# Power.net
KiCad netlist of a schematic drawn in Altium Designer
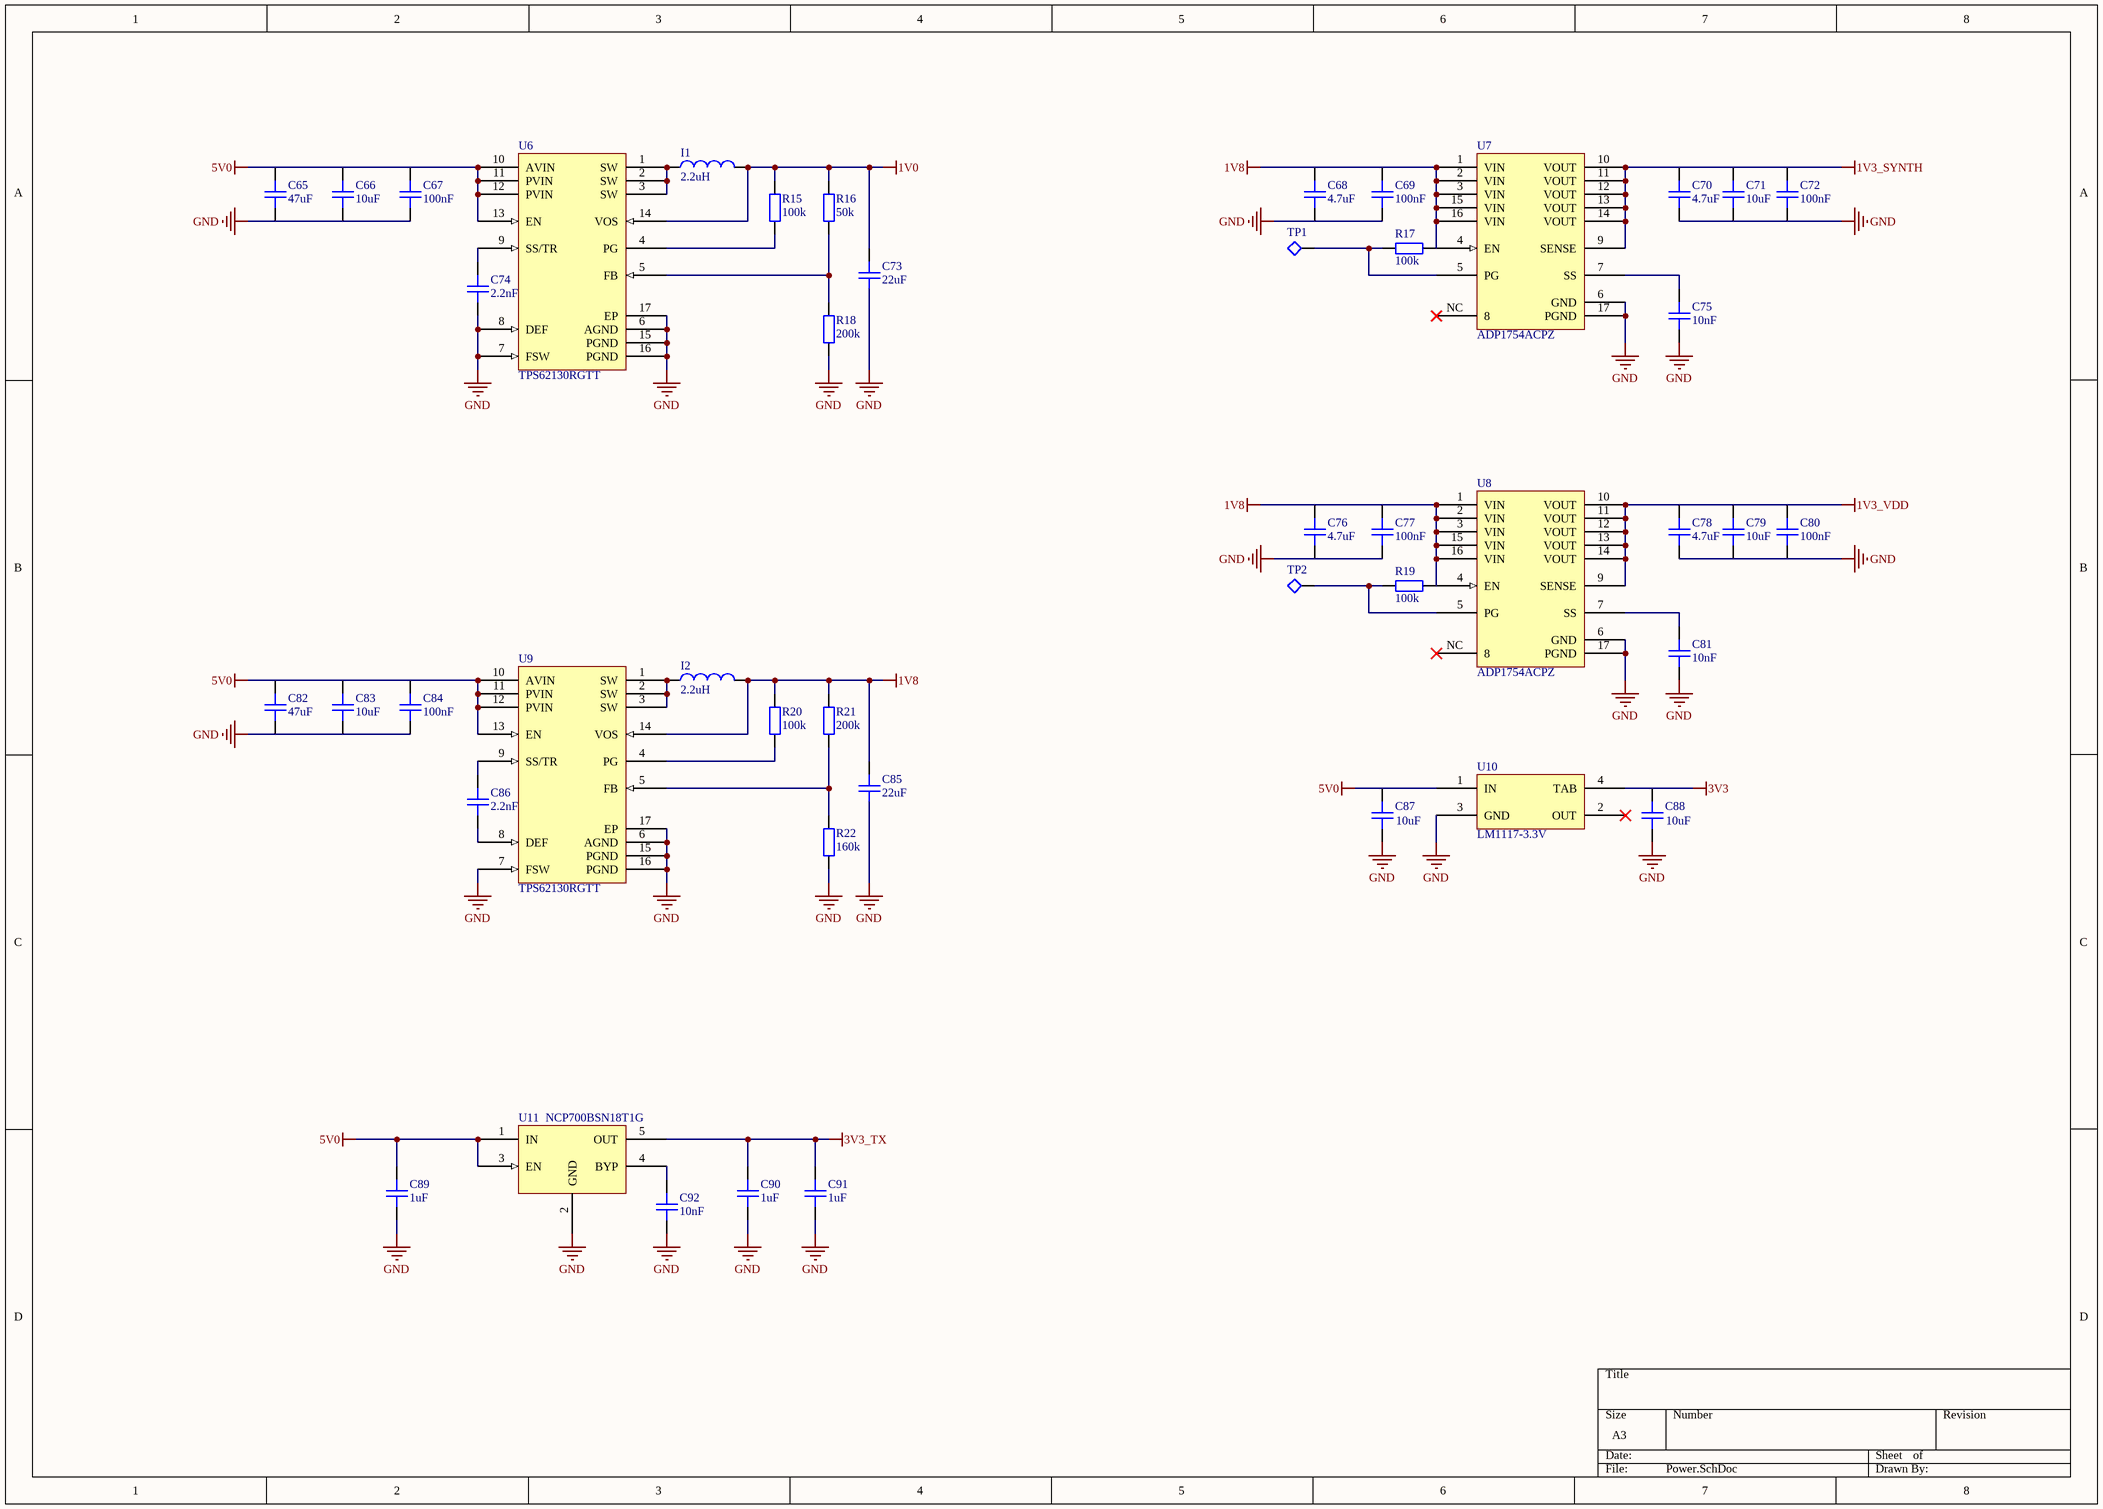
[diagram p0: Power.SchDoc]

(export (version "E")
  (design (tool "Eeschema 10.0.6"))
  (components
    (comp (ref "C65") (value "47uF") (footprint "CAP0402") (libsource (lib "WaveRadio") (part "Cap_0402")))
    (comp (ref "C66") (value "10uF") (footprint "CAP0402") (libsource (lib "WaveRadio") (part "Cap_0402")))
    (comp (ref "C67") (value "100nF") (footprint "CAP0402") (libsource (lib "WaveRadio") (part "Cap_0402")))
    (comp (ref "C68") (value "4.7uF") (footprint "CAP0402") (libsource (lib "WaveRadio") (part "Cap_0402")))
    (comp (ref "C69") (value "100nF") (footprint "CAP0402") (libsource (lib "WaveRadio") (part "Cap_0402")))
    (comp (ref "C70") (value "4.7uF") (footprint "CAP0402") (libsource (lib "WaveRadio") (part "Cap_0402")))
    (comp (ref "C71") (value "10uF") (footprint "CAP0402") (libsource (lib "WaveRadio") (part "Cap_0402")))
    (comp (ref "C72") (value "100nF") (footprint "CAP0402") (libsource (lib "WaveRadio") (part "Cap_0402")))
    (comp (ref "C73") (value "22uF") (footprint "CAP0402") (libsource (lib "WaveRadio") (part "Cap_0402")))
    (comp (ref "C74") (value "2.2nF") (footprint "CAP0402") (libsource (lib "WaveRadio") (part "Cap_0402")))
    (comp (ref "C75") (value "10nF") (footprint "CAP0402") (libsource (lib "WaveRadio") (part "Cap_0402")))
    (comp (ref "C76") (value "4.7uF") (footprint "CAP0402") (libsource (lib "WaveRadio") (part "Cap_0402")))
    (comp (ref "C77") (value "100nF") (footprint "CAP0402") (libsource (lib "WaveRadio") (part "Cap_0402")))
    (comp (ref "C78") (value "4.7uF") (footprint "CAP0402") (libsource (lib "WaveRadio") (part "Cap_0402")))
    (comp (ref "C79") (value "10uF") (footprint "CAP0402") (libsource (lib "WaveRadio") (part "Cap_0402")))
    (comp (ref "C80") (value "100nF") (footprint "CAP0402") (libsource (lib "WaveRadio") (part "Cap_0402")))
    (comp (ref "C81") (value "10nF") (footprint "CAP0402") (libsource (lib "WaveRadio") (part "Cap_0402")))
    (comp (ref "C82") (value "47uF") (footprint "CAP0402") (libsource (lib "WaveRadio") (part "Cap_0402")))
    (comp (ref "C83") (value "10uF") (footprint "CAP0402") (libsource (lib "WaveRadio") (part "Cap_0402")))
    (comp (ref "C84") (value "100nF") (footprint "CAP0402") (libsource (lib "WaveRadio") (part "Cap_0402")))
    (comp (ref "C85") (value "22uF") (footprint "CAP0402") (libsource (lib "WaveRadio") (part "Cap_0402")))
    (comp (ref "C86") (value "2.2nF") (footprint "CAP0402") (libsource (lib "WaveRadio") (part "Cap_0402")))
    (comp (ref "C87") (value "10uF") (footprint "CAP0402") (libsource (lib "WaveRadio") (part "Cap_0402")))
    (comp (ref "C88") (value "10uF") (footprint "CAP0402") (libsource (lib "WaveRadio") (part "Cap_0402")))
    (comp (ref "C89") (value "1uF") (footprint "CAP0402") (libsource (lib "WaveRadio") (part "Cap_0402")))
    (comp (ref "C90") (value "1uF") (footprint "CAP0402") (libsource (lib "WaveRadio") (part "Cap_0402")))
    (comp (ref "C91") (value "1uF") (footprint "CAP0402") (libsource (lib "WaveRadio") (part "Cap_0402")))
    (comp (ref "C92") (value "10nF") (footprint "CAP0402") (libsource (lib "WaveRadio") (part "Cap_0402")))
    (comp (ref "I1")
      (value "2.2uH")
      (fields (field (name "PART") "MLP2012H2R2MT0S1"))
      (libsource (lib "WaveRadio") (part "Ind_0805"))
    )
    (comp (ref "I2")
      (value "2.2uH")
      (fields (field (name "PART") "MLP2012H2R2MT0S1"))
      (libsource (lib "WaveRadio") (part "Ind_0805"))
    )
    (comp (ref "R15") (value "100k") (footprint "RES0402") (libsource (lib "WaveRadio") (part "Res_0402")))
    (comp (ref "R16") (value "50k") (footprint "RES0402") (libsource (lib "WaveRadio") (part "Res_0402")))
    (comp (ref "R17") (value "100k") (footprint "RES0402") (libsource (lib "WaveRadio") (part "Res_0402")))
    (comp (ref "R18") (value "200k") (footprint "RES0402") (libsource (lib "WaveRadio") (part "Res_0402")))
    (comp (ref "R19") (value "100k") (footprint "RES0402") (libsource (lib "WaveRadio") (part "Res_0402")))
    (comp (ref "R20") (value "100k") (footprint "RES0402") (libsource (lib "WaveRadio") (part "Res_0402")))
    (comp (ref "R21") (value "200k") (footprint "RES0402") (libsource (lib "WaveRadio") (part "Res_0402")))
    (comp (ref "R22") (value "160k") (footprint "RES0402") (libsource (lib "WaveRadio") (part "Res_0402")))
    (comp (ref "TP1") (value "TP") (libsource (lib "WaveRadio") (part "TP")))
    (comp (ref "TP2") (value "TP") (libsource (lib "WaveRadio") (part "TP")))
    (comp (ref "U6")
      (value "TPS62130RGTT")
      (footprint "QFN50P300X300X80_HS-17N")
      (libsource (lib "WaveRadio") (part "TPS62130RGTT"))
    )
    (comp (ref "U7")
      (value "ADP1754ACPZ")
      (footprint "QFN65P400X400X80_HS-17N")
      (libsource (lib "WaveRadio") (part "ADP1754ACPZ"))
    )
    (comp (ref "U8")
      (value "ADP1754ACPZ")
      (footprint "QFN65P400X400X80_HS-17N")
      (libsource (lib "WaveRadio") (part "ADP1754ACPZ"))
    )
    (comp (ref "U9")
      (value "TPS62130RGTT")
      (footprint "QFN50P300X300X80_HS-17N")
      (libsource (lib "WaveRadio") (part "TPS62130RGTT"))
    )
    (comp (ref "U10") (value "LM1117-3.3V") (libsource (lib "WaveRadio") (part "LM1117-3.3V")))
    (comp (ref "U11") (value "NCP700BSN18T1G") (libsource (lib "WaveRadio") (part "NCP700BSN18T1G")))
  )
  (nets
    (net (code "1") (name "1V0") (class "Default")
      (node (ref "I1") (pin "2") (pinfunction "2_2") (pintype "passive"))
      (node (ref "U6") (pin "14") (pinfunction "VOS_14") (pintype "input"))
    )
    (net (code "2") (name "1V3_SYNTH") (class "Default")
      (node (ref "U7") (pin "10") (pinfunction "VOUT_10") (pintype "passive"))
      (node (ref "U7") (pin "11") (pinfunction "VOUT_11") (pintype "passive"))
      (node (ref "U7") (pin "12") (pinfunction "VOUT_12") (pintype "passive"))
      (node (ref "U7") (pin "13") (pinfunction "VOUT_13") (pintype "passive"))
      (node (ref "U7") (pin "14") (pinfunction "VOUT_14") (pintype "passive"))
      (node (ref "U7") (pin "9") (pinfunction "SENSE_9") (pintype "passive"))
    )
    (net (code "3") (name "1V3_VDD") (class "Default")
      (node (ref "U8") (pin "10") (pinfunction "VOUT_10") (pintype "passive"))
      (node (ref "U8") (pin "11") (pinfunction "VOUT_11") (pintype "passive"))
      (node (ref "U8") (pin "12") (pinfunction "VOUT_12") (pintype "passive"))
      (node (ref "U8") (pin "13") (pinfunction "VOUT_13") (pintype "passive"))
      (node (ref "U8") (pin "14") (pinfunction "VOUT_14") (pintype "passive"))
      (node (ref "U8") (pin "9") (pinfunction "SENSE_9") (pintype "passive"))
    )
    (net (code "4") (name "1V8") (class "Default")
      (node (ref "I2") (pin "2") (pinfunction "2_2") (pintype "passive"))
      (node (ref "U7") (pin "1") (pinfunction "VIN_1") (pintype "passive"))
      (node (ref "U7") (pin "15") (pinfunction "VIN_15") (pintype "passive"))
      (node (ref "U7") (pin "16") (pinfunction "VIN_16") (pintype "passive"))
      (node (ref "U7") (pin "2") (pinfunction "VIN_2") (pintype "passive"))
      (node (ref "U7") (pin "3") (pinfunction "VIN_3") (pintype "passive"))
      (node (ref "U7") (pin "4") (pinfunction "EN_4") (pintype "input"))
      (node (ref "U8") (pin "1") (pinfunction "VIN_1") (pintype "passive"))
      (node (ref "U8") (pin "15") (pinfunction "VIN_15") (pintype "passive"))
      (node (ref "U8") (pin "16") (pinfunction "VIN_16") (pintype "passive"))
      (node (ref "U8") (pin "2") (pinfunction "VIN_2") (pintype "passive"))
      (node (ref "U8") (pin "3") (pinfunction "VIN_3") (pintype "passive"))
      (node (ref "U8") (pin "4") (pinfunction "EN_4") (pintype "input"))
      (node (ref "U9") (pin "14") (pinfunction "VOS_14") (pintype "input"))
    )
    (net (code "5") (name "3V3") (class "Default")
      (node (ref "U10") (pin "4") (pinfunction "TAB_4") (pintype "passive"))
    )
    (net (code "6") (name "3V3_TX") (class "Default")
      (node (ref "U11") (pin "5") (pinfunction "OUT_5") (pintype "passive"))
    )
    (net (code "7") (name "5V0") (class "Default")
      (node (ref "U10") (pin "1") (pinfunction "IN_1") (pintype "passive"))
      (node (ref "U11") (pin "1") (pinfunction "IN_1") (pintype "passive"))
      (node (ref "U11") (pin "3") (pinfunction "EN_3") (pintype "input"))
      (node (ref "U6") (pin "10") (pinfunction "AVIN_10") (pintype "passive"))
      (node (ref "U6") (pin "11") (pinfunction "PVIN_11") (pintype "passive"))
      (node (ref "U6") (pin "12") (pinfunction "PVIN_12") (pintype "passive"))
      (node (ref "U6") (pin "13") (pinfunction "EN_13") (pintype "input"))
      (node (ref "U9") (pin "10") (pinfunction "AVIN_10") (pintype "passive"))
      (node (ref "U9") (pin "11") (pinfunction "PVIN_11") (pintype "passive"))
      (node (ref "U9") (pin "12") (pinfunction "PVIN_12") (pintype "passive"))
      (node (ref "U9") (pin "13") (pinfunction "EN_13") (pintype "input"))
    )
    (net (code "8") (name "GND") (class "Default")
      (node (ref "C73") (pin "1") (pinfunction "1_1") (pintype "passive"))
      (node (ref "C85") (pin "1") (pinfunction "1_1") (pintype "passive"))
      (node (ref "U10") (pin "3") (pinfunction "GND_3") (pintype "passive"))
      (node (ref "U11") (pin "2") (pinfunction "GND_2") (pintype "passive"))
      (node (ref "U6") (pin "15") (pinfunction "PGND_15") (pintype "passive"))
      (node (ref "U6") (pin "16") (pinfunction "PGND_16") (pintype "passive"))
      (node (ref "U6") (pin "17") (pinfunction "EP_17") (pintype "passive"))
      (node (ref "U6") (pin "6") (pinfunction "AGND_6") (pintype "passive"))
      (node (ref "U6") (pin "7") (pinfunction "FSW_7") (pintype "input"))
      (node (ref "U6") (pin "8") (pinfunction "DEF_8") (pintype "input"))
      (node (ref "U7") (pin "17") (pinfunction "PGND_17") (pintype "passive"))
      (node (ref "U7") (pin "6") (pinfunction "GND_6") (pintype "passive"))
      (node (ref "U8") (pin "17") (pinfunction "PGND_17") (pintype "passive"))
      (node (ref "U8") (pin "6") (pinfunction "GND_6") (pintype "passive"))
      (node (ref "U9") (pin "15") (pinfunction "PGND_15") (pintype "passive"))
      (node (ref "U9") (pin "16") (pinfunction "PGND_16") (pintype "passive"))
      (node (ref "U9") (pin "17") (pinfunction "EP_17") (pintype "passive"))
      (node (ref "U9") (pin "6") (pinfunction "AGND_6") (pintype "passive"))
      (node (ref "U9") (pin "7") (pinfunction "FSW_7") (pintype "input"))
    )
    (net (code "9") (name "Net-(I1-Pad1)") (class "Default")
      (node (ref "I1") (pin "1") (pinfunction "1_1") (pintype "passive"))
      (node (ref "U6") (pin "1") (pinfunction "SW_1") (pintype "passive"))
      (node (ref "U6") (pin "2") (pinfunction "SW_2") (pintype "passive"))
      (node (ref "U6") (pin "3") (pinfunction "SW_3") (pintype "passive"))
    )
    (net (code "10") (name "Net-(I2-Pad1)") (class "Default")
      (node (ref "I2") (pin "1") (pinfunction "1_1") (pintype "passive"))
      (node (ref "U9") (pin "1") (pinfunction "SW_1") (pintype "passive"))
      (node (ref "U9") (pin "2") (pinfunction "SW_2") (pintype "passive"))
      (node (ref "U9") (pin "3") (pinfunction "SW_3") (pintype "passive"))
    )
    (net (code "11") (name "Net-(TP1-NC)") (class "Default")
      (node (ref "TP1") (pin "1") (pinfunction "NC_1") (pintype "passive"))
      (node (ref "U7") (pin "5") (pinfunction "PG_5") (pintype "passive"))
    )
    (net (code "12") (name "Net-(TP2-NC)") (class "Default")
      (node (ref "TP2") (pin "1") (pinfunction "NC_1") (pintype "passive"))
      (node (ref "U8") (pin "5") (pinfunction "PG_5") (pintype "passive"))
    )
    (net (code "13") (name "unconnected-(C65-Pad1)") (class "Default")
      (node (ref "C65") (pin "1") (pinfunction "1_1") (pintype "passive"))
    )
    (net (code "14") (name "unconnected-(C65-Pad2)") (class "Default")
      (node (ref "C65") (pin "2") (pinfunction "2_2") (pintype "passive"))
    )
    (net (code "15") (name "unconnected-(C66-Pad1)") (class "Default")
      (node (ref "C66") (pin "1") (pinfunction "1_1") (pintype "passive"))
    )
    (net (code "16") (name "unconnected-(C66-Pad2)") (class "Default")
      (node (ref "C66") (pin "2") (pinfunction "2_2") (pintype "passive"))
    )
    (net (code "17") (name "unconnected-(C67-Pad1)") (class "Default")
      (node (ref "C67") (pin "1") (pinfunction "1_1") (pintype "passive"))
    )
    (net (code "18") (name "unconnected-(C67-Pad2)") (class "Default")
      (node (ref "C67") (pin "2") (pinfunction "2_2") (pintype "passive"))
    )
    (net (code "19") (name "unconnected-(C68-Pad1)") (class "Default")
      (node (ref "C68") (pin "1") (pinfunction "1_1") (pintype "passive"))
    )
    (net (code "20") (name "unconnected-(C68-Pad2)") (class "Default")
      (node (ref "C68") (pin "2") (pinfunction "2_2") (pintype "passive"))
    )
    (net (code "21") (name "unconnected-(C69-Pad1)") (class "Default")
      (node (ref "C69") (pin "1") (pinfunction "1_1") (pintype "passive"))
    )
    (net (code "22") (name "unconnected-(C69-Pad2)") (class "Default")
      (node (ref "C69") (pin "2") (pinfunction "2_2") (pintype "passive"))
    )
    (net (code "23") (name "unconnected-(C70-Pad1)") (class "Default")
      (node (ref "C70") (pin "1") (pinfunction "1_1") (pintype "passive"))
    )
    (net (code "24") (name "unconnected-(C70-Pad2)") (class "Default")
      (node (ref "C70") (pin "2") (pinfunction "2_2") (pintype "passive"))
    )
    (net (code "25") (name "unconnected-(C71-Pad1)") (class "Default")
      (node (ref "C71") (pin "1") (pinfunction "1_1") (pintype "passive"))
    )
    (net (code "26") (name "unconnected-(C71-Pad2)") (class "Default")
      (node (ref "C71") (pin "2") (pinfunction "2_2") (pintype "passive"))
    )
    (net (code "27") (name "unconnected-(C72-Pad1)") (class "Default")
      (node (ref "C72") (pin "1") (pinfunction "1_1") (pintype "passive"))
    )
    (net (code "28") (name "unconnected-(C72-Pad2)") (class "Default")
      (node (ref "C72") (pin "2") (pinfunction "2_2") (pintype "passive"))
    )
    (net (code "29") (name "unconnected-(C73-Pad2)") (class "Default")
      (node (ref "C73") (pin "2") (pinfunction "2_2") (pintype "passive"))
    )
    (net (code "30") (name "unconnected-(C74-Pad1)") (class "Default")
      (node (ref "C74") (pin "1") (pinfunction "1_1") (pintype "passive"))
    )
    (net (code "31") (name "unconnected-(C74-Pad2)") (class "Default")
      (node (ref "C74") (pin "2") (pinfunction "2_2") (pintype "passive"))
    )
    (net (code "32") (name "unconnected-(C75-Pad1)") (class "Default")
      (node (ref "C75") (pin "1") (pinfunction "1_1") (pintype "passive"))
    )
    (net (code "33") (name "unconnected-(C75-Pad2)") (class "Default")
      (node (ref "C75") (pin "2") (pinfunction "2_2") (pintype "passive"))
    )
    (net (code "34") (name "unconnected-(C76-Pad1)") (class "Default")
      (node (ref "C76") (pin "1") (pinfunction "1_1") (pintype "passive"))
    )
    (net (code "35") (name "unconnected-(C76-Pad2)") (class "Default")
      (node (ref "C76") (pin "2") (pinfunction "2_2") (pintype "passive"))
    )
    (net (code "36") (name "unconnected-(C77-Pad1)") (class "Default")
      (node (ref "C77") (pin "1") (pinfunction "1_1") (pintype "passive"))
    )
    (net (code "37") (name "unconnected-(C77-Pad2)") (class "Default")
      (node (ref "C77") (pin "2") (pinfunction "2_2") (pintype "passive"))
    )
    (net (code "38") (name "unconnected-(C78-Pad1)") (class "Default")
      (node (ref "C78") (pin "1") (pinfunction "1_1") (pintype "passive"))
    )
    (net (code "39") (name "unconnected-(C78-Pad2)") (class "Default")
      (node (ref "C78") (pin "2") (pinfunction "2_2") (pintype "passive"))
    )
    (net (code "40") (name "unconnected-(C79-Pad1)") (class "Default")
      (node (ref "C79") (pin "1") (pinfunction "1_1") (pintype "passive"))
    )
    (net (code "41") (name "unconnected-(C79-Pad2)") (class "Default")
      (node (ref "C79") (pin "2") (pinfunction "2_2") (pintype "passive"))
    )
    (net (code "42") (name "unconnected-(C80-Pad1)") (class "Default")
      (node (ref "C80") (pin "1") (pinfunction "1_1") (pintype "passive"))
    )
    (net (code "43") (name "unconnected-(C80-Pad2)") (class "Default")
      (node (ref "C80") (pin "2") (pinfunction "2_2") (pintype "passive"))
    )
    (net (code "44") (name "unconnected-(C81-Pad1)") (class "Default")
      (node (ref "C81") (pin "1") (pinfunction "1_1") (pintype "passive"))
    )
    (net (code "45") (name "unconnected-(C81-Pad2)") (class "Default")
      (node (ref "C81") (pin "2") (pinfunction "2_2") (pintype "passive"))
    )
    (net (code "46") (name "unconnected-(C82-Pad1)") (class "Default")
      (node (ref "C82") (pin "1") (pinfunction "1_1") (pintype "passive"))
    )
    (net (code "47") (name "unconnected-(C82-Pad2)") (class "Default")
      (node (ref "C82") (pin "2") (pinfunction "2_2") (pintype "passive"))
    )
    (net (code "48") (name "unconnected-(C83-Pad1)") (class "Default")
      (node (ref "C83") (pin "1") (pinfunction "1_1") (pintype "passive"))
    )
    (net (code "49") (name "unconnected-(C83-Pad2)") (class "Default")
      (node (ref "C83") (pin "2") (pinfunction "2_2") (pintype "passive"))
    )
    (net (code "50") (name "unconnected-(C84-Pad1)") (class "Default")
      (node (ref "C84") (pin "1") (pinfunction "1_1") (pintype "passive"))
    )
    (net (code "51") (name "unconnected-(C84-Pad2)") (class "Default")
      (node (ref "C84") (pin "2") (pinfunction "2_2") (pintype "passive"))
    )
    (net (code "52") (name "unconnected-(C85-Pad2)") (class "Default")
      (node (ref "C85") (pin "2") (pinfunction "2_2") (pintype "passive"))
    )
    (net (code "53") (name "unconnected-(C86-Pad1)") (class "Default")
      (node (ref "C86") (pin "1") (pinfunction "1_1") (pintype "passive"))
    )
    (net (code "54") (name "unconnected-(C86-Pad2)") (class "Default")
      (node (ref "C86") (pin "2") (pinfunction "2_2") (pintype "passive"))
    )
    (net (code "55") (name "unconnected-(C87-Pad1)") (class "Default")
      (node (ref "C87") (pin "1") (pinfunction "1_1") (pintype "passive"))
    )
    (net (code "56") (name "unconnected-(C87-Pad2)") (class "Default")
      (node (ref "C87") (pin "2") (pinfunction "2_2") (pintype "passive"))
    )
    (net (code "57") (name "unconnected-(C88-Pad1)") (class "Default")
      (node (ref "C88") (pin "1") (pinfunction "1_1") (pintype "passive"))
    )
    (net (code "58") (name "unconnected-(C88-Pad2)") (class "Default")
      (node (ref "C88") (pin "2") (pinfunction "2_2") (pintype "passive"))
    )
    (net (code "59") (name "unconnected-(C89-Pad1)") (class "Default")
      (node (ref "C89") (pin "1") (pinfunction "1_1") (pintype "passive"))
    )
    (net (code "60") (name "unconnected-(C89-Pad2)") (class "Default")
      (node (ref "C89") (pin "2") (pinfunction "2_2") (pintype "passive"))
    )
    (net (code "61") (name "unconnected-(C90-Pad1)") (class "Default")
      (node (ref "C90") (pin "1") (pinfunction "1_1") (pintype "passive"))
    )
    (net (code "62") (name "unconnected-(C90-Pad2)") (class "Default")
      (node (ref "C90") (pin "2") (pinfunction "2_2") (pintype "passive"))
    )
    (net (code "63") (name "unconnected-(C91-Pad1)") (class "Default")
      (node (ref "C91") (pin "1") (pinfunction "1_1") (pintype "passive"))
    )
    (net (code "64") (name "unconnected-(C91-Pad2)") (class "Default")
      (node (ref "C91") (pin "2") (pinfunction "2_2") (pintype "passive"))
    )
    (net (code "65") (name "unconnected-(C92-Pad1)") (class "Default")
      (node (ref "C92") (pin "1") (pinfunction "1_1") (pintype "passive"))
    )
    (net (code "66") (name "unconnected-(C92-Pad2)") (class "Default")
      (node (ref "C92") (pin "2") (pinfunction "2_2") (pintype "passive"))
    )
    (net (code "67") (name "unconnected-(R15-Pad1)") (class "Default")
      (node (ref "R15") (pin "1") (pintype "passive"))
    )
    (net (code "68") (name "unconnected-(R15-Pad2)") (class "Default")
      (node (ref "R15") (pin "2") (pintype "passive"))
    )
    (net (code "69") (name "unconnected-(R16-Pad1)") (class "Default")
      (node (ref "R16") (pin "1") (pintype "passive"))
    )
    (net (code "70") (name "unconnected-(R16-Pad2)") (class "Default")
      (node (ref "R16") (pin "2") (pintype "passive"))
    )
    (net (code "71") (name "unconnected-(R17-Pad1)") (class "Default")
      (node (ref "R17") (pin "1") (pintype "passive"))
    )
    (net (code "72") (name "unconnected-(R17-Pad2)") (class "Default")
      (node (ref "R17") (pin "2") (pintype "passive"))
    )
    (net (code "73") (name "unconnected-(R18-Pad1)") (class "Default")
      (node (ref "R18") (pin "1") (pintype "passive"))
    )
    (net (code "74") (name "unconnected-(R18-Pad2)") (class "Default")
      (node (ref "R18") (pin "2") (pintype "passive"))
    )
    (net (code "75") (name "unconnected-(R19-Pad1)") (class "Default")
      (node (ref "R19") (pin "1") (pintype "passive"))
    )
    (net (code "76") (name "unconnected-(R19-Pad2)") (class "Default")
      (node (ref "R19") (pin "2") (pintype "passive"))
    )
    (net (code "77") (name "unconnected-(R20-Pad1)") (class "Default")
      (node (ref "R20") (pin "1") (pintype "passive"))
    )
    (net (code "78") (name "unconnected-(R20-Pad2)") (class "Default")
      (node (ref "R20") (pin "2") (pintype "passive"))
    )
    (net (code "79") (name "unconnected-(R21-Pad1)") (class "Default")
      (node (ref "R21") (pin "1") (pintype "passive"))
    )
    (net (code "80") (name "unconnected-(R21-Pad2)") (class "Default")
      (node (ref "R21") (pin "2") (pintype "passive"))
    )
    (net (code "81") (name "unconnected-(R22-Pad1)") (class "Default")
      (node (ref "R22") (pin "1") (pintype "passive"))
    )
    (net (code "82") (name "unconnected-(R22-Pad2)") (class "Default")
      (node (ref "R22") (pin "2") (pintype "passive"))
    )
    (net (code "83") (name "unconnected-(U6-FB-Pad5)") (class "Default")
      (node (ref "U6") (pin "5") (pinfunction "FB_5") (pintype "input"))
    )
    (net (code "84") (name "unconnected-(U6-PG-Pad4)") (class "Default")
      (node (ref "U6") (pin "4") (pinfunction "PG_4") (pintype "passive"))
    )
    (net (code "85") (name "unconnected-(U6-SS{slash}TR-Pad9)") (class "Default")
      (node (ref "U6") (pin "9") (pinfunction "SS/TR_9") (pintype "input"))
    )
    (net (code "86") (name "unconnected-(U7-8-PadNC)") (class "Default")
      (node (ref "U7") (pin "NC") (pinfunction "8_NC") (pintype "passive+no_connect"))
    )
    (net (code "87") (name "unconnected-(U7-SS-Pad7)") (class "Default")
      (node (ref "U7") (pin "7") (pinfunction "SS_7") (pintype "passive"))
    )
    (net (code "88") (name "unconnected-(U8-8-PadNC)") (class "Default")
      (node (ref "U8") (pin "NC") (pinfunction "8_NC") (pintype "passive+no_connect"))
    )
    (net (code "89") (name "unconnected-(U8-SS-Pad7)") (class "Default")
      (node (ref "U8") (pin "7") (pinfunction "SS_7") (pintype "passive"))
    )
    (net (code "90") (name "unconnected-(U9-DEF-Pad8)") (class "Default")
      (node (ref "U9") (pin "8") (pinfunction "DEF_8") (pintype "input"))
    )
    (net (code "91") (name "unconnected-(U9-FB-Pad5)") (class "Default")
      (node (ref "U9") (pin "5") (pinfunction "FB_5") (pintype "input"))
    )
    (net (code "92") (name "unconnected-(U9-PG-Pad4)") (class "Default")
      (node (ref "U9") (pin "4") (pinfunction "PG_4") (pintype "passive"))
    )
    (net (code "93") (name "unconnected-(U9-SS{slash}TR-Pad9)") (class "Default")
      (node (ref "U9") (pin "9") (pinfunction "SS/TR_9") (pintype "input"))
    )
    (net (code "94") (name "unconnected-(U10-OUT-Pad2)") (class "Default")
      (node (ref "U10") (pin "2") (pinfunction "OUT_2") (pintype "passive+no_connect"))
    )
    (net (code "95") (name "unconnected-(U11-BYP-Pad4)") (class "Default")
      (node (ref "U11") (pin "4") (pinfunction "BYP_4") (pintype "passive"))
    )
  )
)
